# 467444_130_3_4-A.net
KiCad netlist of a schematic drawn in Altium Designer
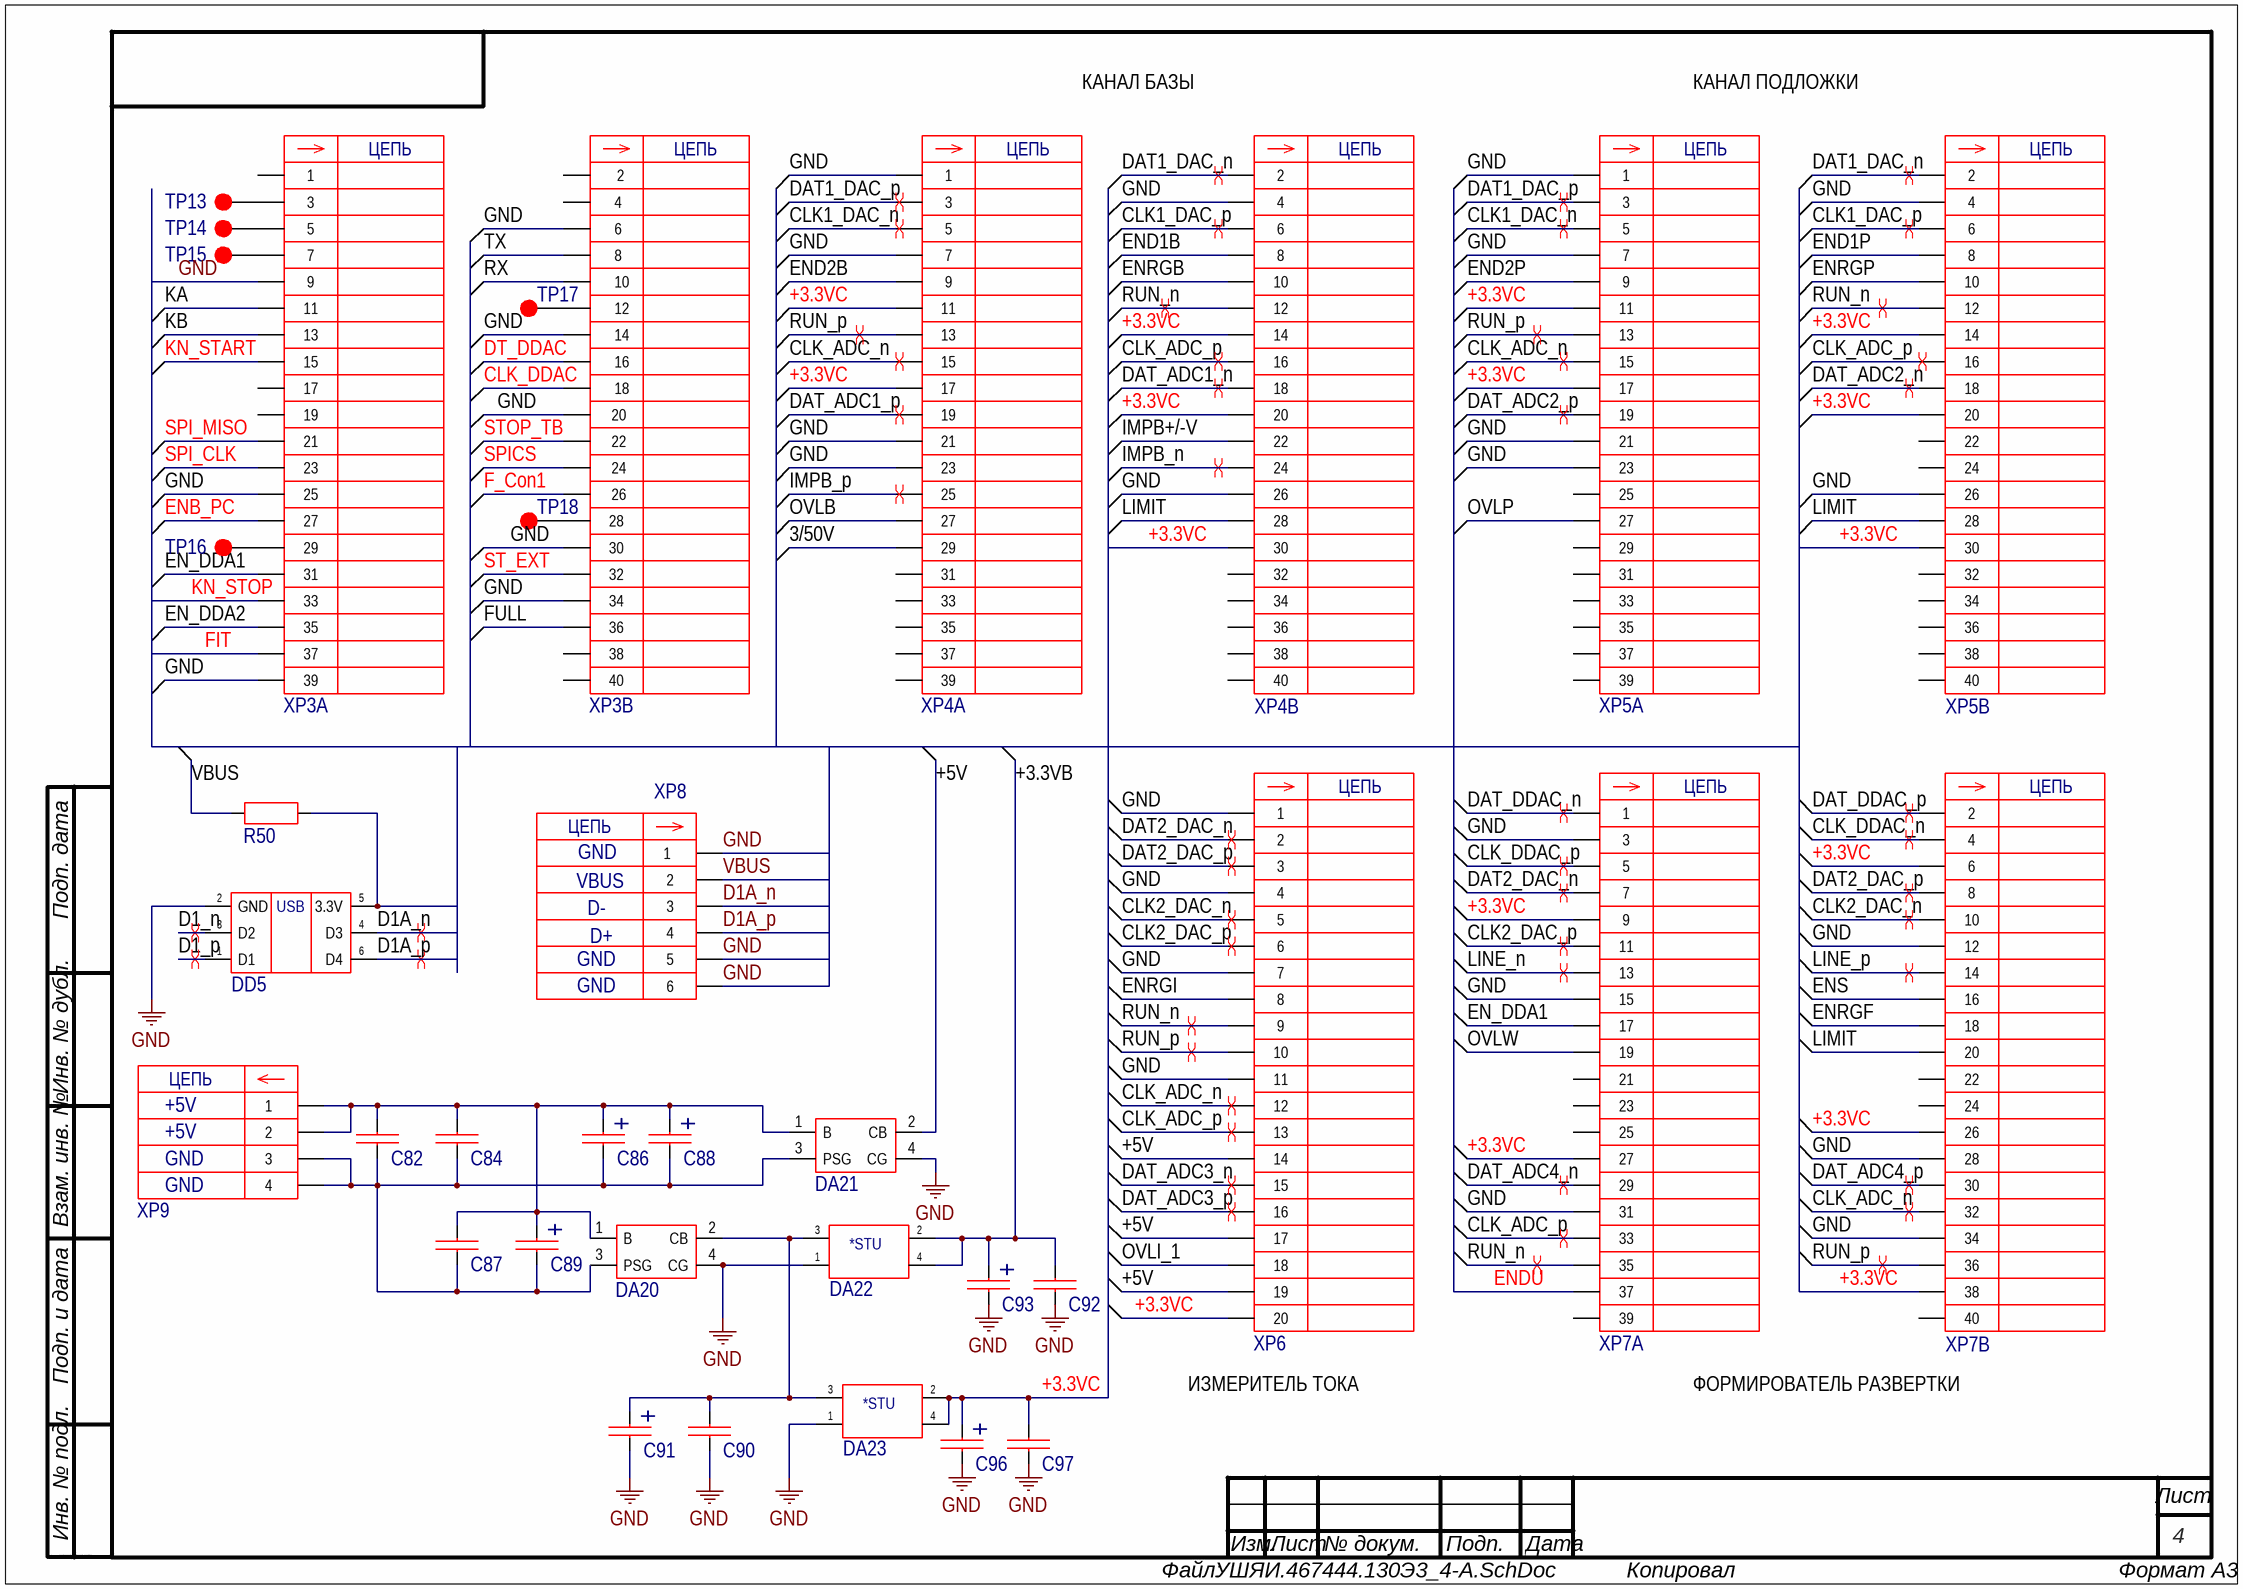
[diagram p0: УШЯИ.467444.130Э3_4-A.SchDoc]

(export (version "E")
  (design (tool "Eeschema 10.0.6"))
  (components
    (comp (ref "C82")
      (value "0,1 µF")
      (footprint "C_0805 [2012 Metric]")
      (description "Неполярный конденсатор")
      (fields (field (name "MANUFACTURER") "Murata") (field (name "VOLTAGE") "50V"))
      (libsource (lib "lib") (part "C_const"))
    )
    (comp (ref "C84")
      (value "0,1 µF")
      (footprint "C_0805 [2012 Metric]")
      (description "Неполярный конденсатор")
      (fields (field (name "MANUFACTURER") "Murata") (field (name "VOLTAGE") "50V"))
      (libsource (lib "lib") (part "C_const"))
    )
    (comp (ref "C86")
      (value "1000 µF")
      (footprint "С_EXR_10x21")
      (description "Полярный конденсатор")
      (fields (field (name "MANUFACTURER") "Hitano") (field (name "VOLTAGE") "16V"))
      (libsource (lib "lib") (part "C_electrolytic"))
    )
    (comp (ref "C87")
      (value "0,1 µF")
      (footprint "C_0805 [2012 Metric]")
      (description "Неполярный конденсатор")
      (fields (field (name "MANUFACTURER") "Murata") (field (name "VOLTAGE") "50V"))
      (libsource (lib "lib") (part "C_const"))
    )
    (comp (ref "C88")
      (value "10 µF")
      (footprint "C+_1210 [3528-21 Metric]")
      (description "Полярный конденсатор")
      (fields (field (name "MANUFACTURER") "KYOCERA AVX") (field (name "VOLTAGE") "20V\r\n10V"))
      (libsource (lib "lib") (part "C_electrolytic"))
    )
    (comp (ref "C89")
      (value "10 µF")
      (footprint "C+_1210 [3528-21 Metric]")
      (description "Полярный конденсатор")
      (fields (field (name "MANUFACTURER") "KYOCERA AVX") (field (name "VOLTAGE") "20V\r\n10V"))
      (libsource (lib "lib") (part "C_electrolytic"))
    )
    (comp (ref "C90")
      (value "0,1 µF")
      (footprint "C_0805 [2012 Metric]")
      (description "Неполярный конденсатор")
      (fields (field (name "MANUFACTURER") "Murata") (field (name "VOLTAGE") "50V"))
      (libsource (lib "lib") (part "C_const"))
    )
    (comp (ref "C91")
      (value "10 µF")
      (footprint "C+_1210 [3528-21 Metric]")
      (description "Полярный конденсатор")
      (fields (field (name "MANUFACTURER") "KYOCERA AVX") (field (name "VOLTAGE") "20V\r\n10V"))
      (libsource (lib "lib") (part "C_electrolytic"))
    )
    (comp (ref "C92")
      (value "0,1 µF")
      (footprint "C_0805 [2012 Metric]")
      (description "Неполярный конденсатор")
      (fields (field (name "MANUFACTURER") "Murata") (field (name "VOLTAGE") "50V"))
      (libsource (lib "lib") (part "C_const"))
    )
    (comp (ref "C93")
      (value "10 µF")
      (footprint "C+_1210 [3528-21 Metric]")
      (description "Полярный конденсатор")
      (fields (field (name "MANUFACTURER") "KYOCERA AVX") (field (name "VOLTAGE") "20V\r\n10V"))
      (libsource (lib "lib") (part "C_electrolytic"))
    )
    (comp (ref "C96")
      (value "10 µF")
      (footprint "C+_1210 [3528-21 Metric]")
      (description "Полярный конденсатор")
      (fields (field (name "MANUFACTURER") "KYOCERA AVX") (field (name "VOLTAGE") "20V\r\n10V"))
      (libsource (lib "lib") (part "C_electrolytic"))
    )
    (comp (ref "C97")
      (value "0,1 µF")
      (footprint "C_0805 [2012 Metric]")
      (description "Неполярный конденсатор")
      (fields (field (name "MANUFACTURER") "Murata") (field (name "VOLTAGE") "50V"))
      (libsource (lib "lib") (part "C_const"))
    )
    (comp (ref "DA20")
      (value "BNX028-01")
      (footprint "F_BNX028-01")
      (description "16В, 35дБ")
      (fields (field (name "MANUFACTURER") "Murata Electronics"))
      (libsource (lib "lib") (part "F_BNX022-01"))
    )
    (comp (ref "DA21")
      (value "BNX028-01")
      (footprint "F_BNX028-01")
      (description "16В, 35дБ")
      (fields (field (name "MANUFACTURER") "Murata Electronics"))
      (libsource (lib "lib") (part "F_BNX022-01"))
    )
    (comp (ref "DA22")
      (value "LD1117AS33TR")
      (footprint "SOT-223")
      (description "IC, Fixed LDO Voltage Regulator, 5.3V to 10V, 1.15V Dropout, 3.3Vout, 1Aout")
      (fields (field (name "MANUFACTURER") "STMicroelectronics"))
      (libsource (lib "lib") (part "VolReg_LD1117AS33TR"))
    )
    (comp (ref "DA23")
      (value "LD1117AS33TR")
      (footprint "SOT-223")
      (description "IC, Fixed LDO Voltage Regulator, 5.3V to 10V, 1.15V Dropout, 3.3Vout, 1Aout")
      (fields (field (name "MANUFACTURER") "STMicroelectronics"))
      (libsource (lib "lib") (part "VolReg_LD1117AS33TR"))
    )
    (comp (ref "DD5")
      (value "USBUF01W6")
      (footprint "SOT-323-6")
      (description "EMI Filter, 2-Channel, USB Upstream Terminator, ESD Protection")
      (fields (field (name "MANUFACTURER") "STMicroelectronics"))
      (libsource (lib "lib") (part "USBUF01W6"))
    )
    (comp (ref "R50")
      (value "30R")
      (footprint "R_0805 [2012 Metric]")
      (fields (field (name "TOLERANCE") "±5%"))
      (libsource (lib "lib") (part "R_Const"))
    )
    (comp (ref "TP13") (value "~") (footprint "DSP_1.3") (libsource (lib "lib") (part "TP")))
    (comp (ref "TP14") (value "~") (footprint "DSP_1.3") (libsource (lib "lib") (part "TP")))
    (comp (ref "TP15") (value "~") (footprint "DSP_1.3") (libsource (lib "lib") (part "TP")))
    (comp (ref "TP16") (value "~") (footprint "DSP_1.3") (libsource (lib "lib") (part "TP")))
    (comp (ref "TP17") (value "~") (footprint "DSP_1.3") (libsource (lib "lib") (part "TP")))
    (comp (ref "TP18") (value "~") (footprint "DSP_1.3") (libsource (lib "lib") (part "TP")))
    (comp (ref "XP3")
      (value "BH-40")
      (footprint "BH-40")
      (description "Male, 40 pins, 2 rows, Vertical")
      (fields (field (name "MANUFACTURER") "Connfly electronic"))
      (libsource (lib "lib") (part "M_40"))
    )
    (comp (ref "XP4")
      (value "BH2-40")
      (footprint "BH2-40")
      (description "Male, 40 pins, 2 rows, Vertical, DS1014-40, 2 mm")
      (fields (field (name "MANUFACTURER") "Connfly electronic"))
      (libsource (lib "lib") (part "M_40"))
    )
    (comp (ref "XP5")
      (value "BH2-40")
      (footprint "BH2-40")
      (description "Male, 40 pins, 2 rows, Vertical, DS1014-40, 2 mm")
      (fields (field (name "MANUFACTURER") "Connfly electronic"))
      (libsource (lib "lib") (part "M_40"))
    )
    (comp (ref "XP6")
      (value "BH2-20R")
      (footprint "BH2-20R")
      (description "Male, 20 pins, 2 rows, Right Angle, DS1014-20RF1B-B, 2 mm")
      (fields (field (name "MANUFACTURER") "Connfly electronic"))
      (libsource (lib "lib") (part "M_20"))
    )
    (comp (ref "XP7")
      (value "BH2-40")
      (footprint "BH2-40")
      (description "Male, 40 pins, 2 rows, Vertical, DS1014-40, 2 mm")
      (fields (field (name "MANUFACTURER") "Connfly electronic"))
      (libsource (lib "lib") (part "M_40"))
    )
    (comp (ref "XP8")
      (value "AMPMODU II 280372-2")
      (footprint "AMP II-280372-2")
      (description "Male, 6 pin, 1 row, Vertical, Board-to-Board, 2.54 mm")
      (fields (field (name "MANUFACTURER") "TE Connectivity"))
      (libsource (lib "Lib_MN") (part "M_6"))
    )
    (comp (ref "XP9")
      (value "AMPMODU II 280371-2")
      (footprint "AMP II-280371-2")
      (description "Male, 4 pin, 1 row, Vertical, Board-to-Board, 2.54 mm")
      (fields (field (name "MANUFACTURER") "TE Connectivity"))
      (libsource (lib "lib") (part "M_4"))
    )
  )
  (nets
    (net (code "1") (name "/+3.3VB") (class "Default")
      (node (ref "C92") (pin "2") (pinfunction "2_2") (pintype "passive"))
      (node (ref "C93") (pin "+") (pinfunction "+_+") (pintype "passive"))
      (node (ref "DA22") (pin "2") (pinfunction "VOUT_2") (pintype "passive"))
      (node (ref "DA22") (pin "4") (pinfunction "VOUT_4") (pintype "passive"))
    )
    (net (code "2") (name "/+3.3VC") (class "Default")
      (node (ref "C96") (pin "+") (pinfunction "+_+") (pintype "passive"))
      (node (ref "C97") (pin "2") (pinfunction "2_2") (pintype "passive"))
      (node (ref "DA23") (pin "2") (pinfunction "VOUT_2") (pintype "passive"))
      (node (ref "DA23") (pin "4") (pinfunction "VOUT_4") (pintype "passive"))
      (node (ref "XP4") (pin "11") (pinfunction "11_11") (pintype "passive"))
      (node (ref "XP4") (pin "14") (pinfunction "14_14") (pintype "passive"))
      (node (ref "XP4") (pin "17") (pinfunction "17_17") (pintype "passive"))
      (node (ref "XP4") (pin "20") (pinfunction "20_20") (pintype "passive"))
      (node (ref "XP4") (pin "30") (pinfunction "30_30") (pintype "passive"))
      (node (ref "XP5") (pin "11") (pinfunction "11_11") (pintype "passive"))
      (node (ref "XP5") (pin "14") (pinfunction "14_14") (pintype "passive"))
      (node (ref "XP5") (pin "17") (pinfunction "17_17") (pintype "passive"))
      (node (ref "XP5") (pin "20") (pinfunction "20_20") (pintype "passive"))
      (node (ref "XP5") (pin "30") (pinfunction "30_30") (pintype "passive"))
      (node (ref "XP6") (pin "20") (pinfunction "20_20") (pintype "passive"))
      (node (ref "XP7") (pin "26") (pinfunction "26_26") (pintype "passive"))
      (node (ref "XP7") (pin "27") (pinfunction "27_27") (pintype "passive"))
      (node (ref "XP7") (pin "38") (pinfunction "38_38") (pintype "passive"))
      (node (ref "XP7") (pin "6") (pinfunction "6_6") (pintype "passive"))
      (node (ref "XP7") (pin "9") (pinfunction "9_9") (pintype "passive"))
    )
    (net (code "3") (name "/+5V") (class "Default")
      (node (ref "DA21") (pin "2") (pinfunction "CB_2") (pintype "passive"))
      (node (ref "XP6") (pin "14") (pinfunction "14_14") (pintype "passive"))
      (node (ref "XP6") (pin "17") (pinfunction "17_17") (pintype "passive"))
      (node (ref "XP6") (pin "19") (pinfunction "19_19") (pintype "passive"))
    )
    (net (code "4") (name "/3{slash}50V") (class "Default")
      (node (ref "XP4") (pin "29") (pinfunction "29_29") (pintype "passive"))
    )
    (net (code "5") (name "/CLK1_DAC_n") (class "Default")
      (node (ref "XP4") (pin "5") (pinfunction "5_5") (pintype "passive"))
      (node (ref "XP5") (pin "5") (pinfunction "5_5") (pintype "passive"))
    )
    (net (code "6") (name "/CLK1_DAC_p") (class "Default")
      (node (ref "XP4") (pin "6") (pinfunction "6_6") (pintype "passive"))
      (node (ref "XP5") (pin "6") (pinfunction "6_6") (pintype "passive"))
    )
    (net (code "7") (name "/CLK2_DAC_n") (class "Default")
      (node (ref "XP6") (pin "5") (pinfunction "5_5") (pintype "passive"))
      (node (ref "XP7") (pin "10") (pinfunction "10_10") (pintype "passive"))
    )
    (net (code "8") (name "/CLK2_DAC_p") (class "Default")
      (node (ref "XP6") (pin "6") (pinfunction "6_6") (pintype "passive"))
      (node (ref "XP7") (pin "11") (pinfunction "11_11") (pintype "passive"))
    )
    (net (code "9") (name "/CLK_ADC_n") (class "Default")
      (node (ref "XP4") (pin "15") (pinfunction "15_15") (pintype "passive"))
      (node (ref "XP5") (pin "15") (pinfunction "15_15") (pintype "passive"))
      (node (ref "XP6") (pin "12") (pinfunction "12_12") (pintype "passive"))
      (node (ref "XP7") (pin "32") (pinfunction "32_32") (pintype "passive"))
    )
    (net (code "10") (name "/CLK_ADC_p") (class "Default")
      (node (ref "XP4") (pin "16") (pinfunction "16_16") (pintype "passive"))
      (node (ref "XP5") (pin "16") (pinfunction "16_16") (pintype "passive"))
      (node (ref "XP6") (pin "13") (pinfunction "13_13") (pintype "passive"))
      (node (ref "XP7") (pin "33") (pinfunction "33_33") (pintype "passive"))
    )
    (net (code "11") (name "/CLK_DDAC") (class "Default")
      (node (ref "XP3") (pin "18") (pinfunction "18_18") (pintype "passive"))
    )
    (net (code "12") (name "/CLK_DDAC_n") (class "Default")
      (node (ref "XP7") (pin "4") (pinfunction "4_4") (pintype "passive"))
    )
    (net (code "13") (name "/CLK_DDAC_p") (class "Default")
      (node (ref "XP7") (pin "5") (pinfunction "5_5") (pintype "passive"))
    )
    (net (code "14") (name "/D1A_n") (class "Default")
      (node (ref "DD5") (pin "4") (pinfunction "D3_4") (pintype "passive"))
      (node (ref "XP8") (pin "3") (pinfunction "3_3") (pintype "passive"))
    )
    (net (code "15") (name "/D1A_p") (class "Default")
      (node (ref "DD5") (pin "6") (pinfunction "D4_6") (pintype "passive"))
      (node (ref "XP8") (pin "4") (pinfunction "4_4") (pintype "passive"))
    )
    (net (code "16") (name "/D1_n") (class "Default")
      (node (ref "DD5") (pin "3") (pinfunction "D2_3") (pintype "passive"))
    )
    (net (code "17") (name "/D1_p") (class "Default")
      (node (ref "DD5") (pin "1") (pinfunction "D1_1") (pintype "passive"))
    )
    (net (code "18") (name "/DAT1_DAC_n") (class "Default")
      (node (ref "XP4") (pin "2") (pinfunction "2_2") (pintype "passive"))
      (node (ref "XP5") (pin "2") (pinfunction "2_2") (pintype "passive"))
    )
    (net (code "19") (name "/DAT1_DAC_p") (class "Default")
      (node (ref "XP4") (pin "3") (pinfunction "3_3") (pintype "passive"))
      (node (ref "XP5") (pin "3") (pinfunction "3_3") (pintype "passive"))
    )
    (net (code "20") (name "/DAT2_DAC_n") (class "Default")
      (node (ref "XP6") (pin "2") (pinfunction "2_2") (pintype "passive"))
      (node (ref "XP7") (pin "7") (pinfunction "7_7") (pintype "passive"))
    )
    (net (code "21") (name "/DAT2_DAC_p") (class "Default")
      (node (ref "XP6") (pin "3") (pinfunction "3_3") (pintype "passive"))
      (node (ref "XP7") (pin "8") (pinfunction "8_8") (pintype "passive"))
    )
    (net (code "22") (name "/DAT_ADC1_n") (class "Default")
      (node (ref "XP4") (pin "18") (pinfunction "18_18") (pintype "passive"))
    )
    (net (code "23") (name "/DAT_ADC1_p") (class "Default")
      (node (ref "XP4") (pin "19") (pinfunction "19_19") (pintype "passive"))
    )
    (net (code "24") (name "/DAT_ADC2_n") (class "Default")
      (node (ref "XP5") (pin "18") (pinfunction "18_18") (pintype "passive"))
    )
    (net (code "25") (name "/DAT_ADC2_p") (class "Default")
      (node (ref "XP5") (pin "19") (pinfunction "19_19") (pintype "passive"))
    )
    (net (code "26") (name "/DAT_ADC3_n") (class "Default")
      (node (ref "XP6") (pin "15") (pinfunction "15_15") (pintype "passive"))
    )
    (net (code "27") (name "/DAT_ADC3_p") (class "Default")
      (node (ref "XP6") (pin "16") (pinfunction "16_16") (pintype "passive"))
    )
    (net (code "28") (name "/DAT_ADC4_n") (class "Default")
      (node (ref "XP7") (pin "29") (pinfunction "29_29") (pintype "passive"))
    )
    (net (code "29") (name "/DAT_ADC4_p") (class "Default")
      (node (ref "XP7") (pin "30") (pinfunction "30_30") (pintype "passive"))
    )
    (net (code "30") (name "/DAT_DDAC_n") (class "Default")
      (node (ref "XP7") (pin "1") (pinfunction "1_1") (pintype "passive"))
    )
    (net (code "31") (name "/DAT_DDAC_p") (class "Default")
      (node (ref "XP7") (pin "2") (pinfunction "2_2") (pintype "passive"))
    )
    (net (code "32") (name "/DT_DDAC") (class "Default")
      (node (ref "XP3") (pin "16") (pinfunction "16_16") (pintype "passive"))
    )
    (net (code "33") (name "/ENB_PC") (class "Default")
      (node (ref "XP3") (pin "27") (pinfunction "27_27") (pintype "passive"))
    )
    (net (code "34") (name "/END1B") (class "Default")
      (node (ref "XP4") (pin "8") (pinfunction "8_8") (pintype "passive"))
    )
    (net (code "35") (name "/END1P") (class "Default")
      (node (ref "XP5") (pin "8") (pinfunction "8_8") (pintype "passive"))
    )
    (net (code "36") (name "/END2B") (class "Default")
      (node (ref "XP4") (pin "9") (pinfunction "9_9") (pintype "passive"))
    )
    (net (code "37") (name "/END2P") (class "Default")
      (node (ref "XP5") (pin "9") (pinfunction "9_9") (pintype "passive"))
    )
    (net (code "38") (name "/ENDU") (class "Default")
      (node (ref "XP7") (pin "37") (pinfunction "37_37") (pintype "passive"))
    )
    (net (code "39") (name "/ENRGB") (class "Default")
      (node (ref "XP4") (pin "10") (pinfunction "10_10") (pintype "passive"))
    )
    (net (code "40") (name "/ENRGF") (class "Default")
      (node (ref "XP7") (pin "18") (pinfunction "18_18") (pintype "passive"))
    )
    (net (code "41") (name "/ENRGI") (class "Default")
      (node (ref "XP6") (pin "8") (pinfunction "8_8") (pintype "passive"))
    )
    (net (code "42") (name "/ENRGP") (class "Default")
      (node (ref "XP5") (pin "10") (pinfunction "10_10") (pintype "passive"))
    )
    (net (code "43") (name "/ENS") (class "Default")
      (node (ref "XP7") (pin "16") (pinfunction "16_16") (pintype "passive"))
    )
    (net (code "44") (name "/EN_DDA1") (class "Default")
      (node (ref "XP3") (pin "31") (pinfunction "31_31") (pintype "passive"))
      (node (ref "XP7") (pin "17") (pinfunction "17_17") (pintype "passive"))
    )
    (net (code "45") (name "/EN_DDA2") (class "Default")
      (node (ref "XP3") (pin "35") (pinfunction "35_35") (pintype "passive"))
    )
    (net (code "46") (name "/FIT") (class "Default")
      (node (ref "XP3") (pin "37") (pinfunction "37_37") (pintype "passive"))
    )
    (net (code "47") (name "/FULL") (class "Default")
      (node (ref "XP3") (pin "36") (pinfunction "36_36") (pintype "passive"))
    )
    (net (code "48") (name "/F_Con1") (class "Default")
      (node (ref "XP3") (pin "26") (pinfunction "26_26") (pintype "passive"))
    )
    (net (code "49") (name "/IMPB+{slash}-V") (class "Default")
      (node (ref "XP4") (pin "22") (pinfunction "22_22") (pintype "passive"))
    )
    (net (code "50") (name "/IMPB_n") (class "Default")
      (node (ref "XP4") (pin "24") (pinfunction "24_24") (pintype "passive"))
    )
    (net (code "51") (name "/IMPB_p") (class "Default")
      (node (ref "XP4") (pin "25") (pinfunction "25_25") (pintype "passive"))
    )
    (net (code "52") (name "/KA") (class "Default")
      (node (ref "XP3") (pin "11") (pinfunction "11_11") (pintype "passive"))
    )
    (net (code "53") (name "/KB") (class "Default")
      (node (ref "XP3") (pin "13") (pinfunction "13_13") (pintype "passive"))
    )
    (net (code "54") (name "/KN_START") (class "Default")
      (node (ref "XP3") (pin "15") (pinfunction "15_15") (pintype "passive"))
    )
    (net (code "55") (name "/KN_STOP") (class "Default")
      (node (ref "XP3") (pin "33") (pinfunction "33_33") (pintype "passive"))
    )
    (net (code "56") (name "/LIMIT") (class "Default")
      (node (ref "XP4") (pin "28") (pinfunction "28_28") (pintype "passive"))
      (node (ref "XP5") (pin "28") (pinfunction "28_28") (pintype "passive"))
      (node (ref "XP7") (pin "20") (pinfunction "20_20") (pintype "passive"))
    )
    (net (code "57") (name "/LINE_n") (class "Default")
      (node (ref "XP7") (pin "13") (pinfunction "13_13") (pintype "passive"))
    )
    (net (code "58") (name "/LINE_p") (class "Default")
      (node (ref "XP7") (pin "14") (pinfunction "14_14") (pintype "passive"))
    )
    (net (code "59") (name "/OVLB") (class "Default")
      (node (ref "XP4") (pin "27") (pinfunction "27_27") (pintype "passive"))
    )
    (net (code "60") (name "/OVLI_1") (class "Default")
      (node (ref "XP6") (pin "18") (pinfunction "18_18") (pintype "passive"))
    )
    (net (code "61") (name "/OVLP") (class "Default")
      (node (ref "XP5") (pin "27") (pinfunction "27_27") (pintype "passive"))
    )
    (net (code "62") (name "/OVLW") (class "Default")
      (node (ref "XP7") (pin "19") (pinfunction "19_19") (pintype "passive"))
    )
    (net (code "63") (name "/RUN_n") (class "Default")
      (node (ref "XP4") (pin "12") (pinfunction "12_12") (pintype "passive"))
      (node (ref "XP5") (pin "12") (pinfunction "12_12") (pintype "passive"))
      (node (ref "XP6") (pin "9") (pinfunction "9_9") (pintype "passive"))
      (node (ref "XP7") (pin "35") (pinfunction "35_35") (pintype "passive"))
    )
    (net (code "64") (name "/RUN_p") (class "Default")
      (node (ref "XP4") (pin "13") (pinfunction "13_13") (pintype "passive"))
      (node (ref "XP5") (pin "13") (pinfunction "13_13") (pintype "passive"))
      (node (ref "XP6") (pin "10") (pinfunction "10_10") (pintype "passive"))
      (node (ref "XP7") (pin "36") (pinfunction "36_36") (pintype "passive"))
    )
    (net (code "65") (name "/RX") (class "Default")
      (node (ref "XP3") (pin "10") (pinfunction "10_10") (pintype "passive"))
    )
    (net (code "66") (name "/SPICS") (class "Default")
      (node (ref "XP3") (pin "24") (pinfunction "24_24") (pintype "passive"))
    )
    (net (code "67") (name "/SPI_CLK") (class "Default")
      (node (ref "XP3") (pin "23") (pinfunction "23_23") (pintype "passive"))
    )
    (net (code "68") (name "/SPI_MISO") (class "Default")
      (node (ref "XP3") (pin "21") (pinfunction "21_21") (pintype "passive"))
    )
    (net (code "69") (name "/STOP_TB") (class "Default")
      (node (ref "XP3") (pin "22") (pinfunction "22_22") (pintype "passive"))
    )
    (net (code "70") (name "/ST_EXT") (class "Default")
      (node (ref "XP3") (pin "32") (pinfunction "32_32") (pintype "passive"))
    )
    (net (code "71") (name "/TX") (class "Default")
      (node (ref "XP3") (pin "8") (pinfunction "8_8") (pintype "passive"))
    )
    (net (code "72") (name "/VBUS") (class "Default")
      (node (ref "R50") (pin "1") (pinfunction "1_1") (pintype "passive"))
      (node (ref "XP8") (pin "2") (pinfunction "2_2") (pintype "passive"))
    )
    (net (code "73") (name "GND") (class "Default")
      (node (ref "C90") (pin "2") (pinfunction "2_2") (pintype "passive"))
      (node (ref "C91") (pin "-") (pinfunction "-_-") (pintype "passive"))
      (node (ref "C92") (pin "1") (pinfunction "1_1") (pintype "passive"))
      (node (ref "C93") (pin "-") (pinfunction "-_-") (pintype "passive"))
      (node (ref "C96") (pin "-") (pinfunction "-_-") (pintype "passive"))
      (node (ref "C97") (pin "1") (pinfunction "1_1") (pintype "passive"))
      (node (ref "DA20") (pin "4") (pinfunction "CG_4") (pintype "passive"))
      (node (ref "DA21") (pin "4") (pinfunction "CG_4") (pintype "passive"))
      (node (ref "DA22") (pin "1") (pinfunction "ADJ/GND_1") (pintype "passive"))
      (node (ref "DA23") (pin "1") (pinfunction "ADJ/GND_1") (pintype "passive"))
      (node (ref "DD5") (pin "2") (pinfunction "GND_2") (pintype "passive"))
      (node (ref "XP3") (pin "14") (pinfunction "14_14") (pintype "passive"))
      (node (ref "XP3") (pin "20") (pinfunction "20_20") (pintype "passive"))
      (node (ref "XP3") (pin "25") (pinfunction "25_25") (pintype "passive"))
      (node (ref "XP3") (pin "30") (pinfunction "30_30") (pintype "passive"))
      (node (ref "XP3") (pin "34") (pinfunction "34_34") (pintype "passive"))
      (node (ref "XP3") (pin "39") (pinfunction "39_39") (pintype "passive"))
      (node (ref "XP3") (pin "6") (pinfunction "6_6") (pintype "passive"))
      (node (ref "XP3") (pin "9") (pinfunction "9_9") (pintype "passive"))
      (node (ref "XP4") (pin "1") (pinfunction "1_1") (pintype "passive"))
      (node (ref "XP4") (pin "21") (pinfunction "21_21") (pintype "passive"))
      (node (ref "XP4") (pin "23") (pinfunction "23_23") (pintype "passive"))
      (node (ref "XP4") (pin "26") (pinfunction "26_26") (pintype "passive"))
      (node (ref "XP4") (pin "4") (pinfunction "4_4") (pintype "passive"))
      (node (ref "XP4") (pin "7") (pinfunction "7_7") (pintype "passive"))
      (node (ref "XP5") (pin "1") (pinfunction "1_1") (pintype "passive"))
      (node (ref "XP5") (pin "21") (pinfunction "21_21") (pintype "passive"))
      (node (ref "XP5") (pin "23") (pinfunction "23_23") (pintype "passive"))
      (node (ref "XP5") (pin "26") (pinfunction "26_26") (pintype "passive"))
      (node (ref "XP5") (pin "4") (pinfunction "4_4") (pintype "passive"))
      (node (ref "XP5") (pin "7") (pinfunction "7_7") (pintype "passive"))
      (node (ref "XP6") (pin "1") (pinfunction "1_1") (pintype "passive"))
      (node (ref "XP6") (pin "11") (pinfunction "11_11") (pintype "passive"))
      (node (ref "XP6") (pin "4") (pinfunction "4_4") (pintype "passive"))
      (node (ref "XP6") (pin "7") (pinfunction "7_7") (pintype "passive"))
      (node (ref "XP7") (pin "12") (pinfunction "12_12") (pintype "passive"))
      (node (ref "XP7") (pin "15") (pinfunction "15_15") (pintype "passive"))
      (node (ref "XP7") (pin "28") (pinfunction "28_28") (pintype "passive"))
      (node (ref "XP7") (pin "3") (pinfunction "3_3") (pintype "passive"))
      (node (ref "XP7") (pin "31") (pinfunction "31_31") (pintype "passive"))
      (node (ref "XP7") (pin "34") (pinfunction "34_34") (pintype "passive"))
      (node (ref "XP8") (pin "1") (pinfunction "1_1") (pintype "passive"))
      (node (ref "XP8") (pin "5") (pinfunction "5_5") (pintype "passive"))
      (node (ref "XP8") (pin "6") (pinfunction "6_6") (pintype "passive"))
    )
    (net (code "74") (name "Net-(DA20-B)") (class "Default")
      (node (ref "C82") (pin "1") (pinfunction "1_1") (pintype "passive"))
      (node (ref "C84") (pin "1") (pinfunction "1_1") (pintype "passive"))
      (node (ref "C86") (pin "+") (pinfunction "+_+") (pintype "passive"))
      (node (ref "C87") (pin "2") (pinfunction "2_2") (pintype "passive"))
      (node (ref "C88") (pin "+") (pinfunction "+_+") (pintype "passive"))
      (node (ref "C89") (pin "+") (pinfunction "+_+") (pintype "passive"))
      (node (ref "DA20") (pin "1") (pinfunction "B_1") (pintype "passive"))
      (node (ref "DA21") (pin "1") (pinfunction "B_1") (pintype "passive"))
      (node (ref "XP9") (pin "1") (pinfunction "1_1") (pintype "passive"))
      (node (ref "XP9") (pin "2") (pinfunction "2_2") (pintype "passive"))
    )
    (net (code "75") (name "Net-(DA20-CB)") (class "Default")
      (node (ref "C90") (pin "1") (pinfunction "1_1") (pintype "passive"))
      (node (ref "C91") (pin "+") (pinfunction "+_+") (pintype "passive"))
      (node (ref "DA20") (pin "2") (pinfunction "CB_2") (pintype "passive"))
      (node (ref "DA22") (pin "3") (pinfunction "VIN_3") (pintype "passive"))
      (node (ref "DA23") (pin "3") (pinfunction "VIN_3") (pintype "passive"))
    )
    (net (code "76") (name "Net-(DA20-PSG)") (class "Default")
      (node (ref "C82") (pin "2") (pinfunction "2_2") (pintype "passive"))
      (node (ref "C84") (pin "2") (pinfunction "2_2") (pintype "passive"))
      (node (ref "C86") (pin "-") (pinfunction "-_-") (pintype "passive"))
      (node (ref "C87") (pin "1") (pinfunction "1_1") (pintype "passive"))
      (node (ref "C88") (pin "-") (pinfunction "-_-") (pintype "passive"))
      (node (ref "C89") (pin "-") (pinfunction "-_-") (pintype "passive"))
      (node (ref "DA20") (pin "3") (pinfunction "PSG_3") (pintype "passive"))
      (node (ref "DA21") (pin "3") (pinfunction "PSG_3") (pintype "passive"))
      (node (ref "XP9") (pin "3") (pinfunction "3_3") (pintype "passive"))
      (node (ref "XP9") (pin "4") (pinfunction "4_4") (pintype "passive"))
    )
    (net (code "77") (name "Net-(DD5-3.3V)") (class "Default")
      (node (ref "DD5") (pin "5") (pinfunction "3.3V_5") (pintype "passive"))
      (node (ref "R50") (pin "2") (pinfunction "2_2") (pintype "passive"))
    )
    (net (code "78") (name "Net-(TP13-Pad1)") (class "Default")
      (node (ref "TP13") (pin "1") (pinfunction "1_1") (pintype "passive"))
      (node (ref "XP3") (pin "3") (pinfunction "3_3") (pintype "passive"))
    )
    (net (code "79") (name "Net-(TP14-Pad1)") (class "Default")
      (node (ref "TP14") (pin "1") (pinfunction "1_1") (pintype "passive"))
      (node (ref "XP3") (pin "5") (pinfunction "5_5") (pintype "passive"))
    )
    (net (code "80") (name "Net-(TP15-Pad1)") (class "Default")
      (node (ref "TP15") (pin "1") (pinfunction "1_1") (pintype "passive"))
      (node (ref "XP3") (pin "7") (pinfunction "7_7") (pintype "passive"))
    )
    (net (code "81") (name "Net-(TP16-Pad1)") (class "Default")
      (node (ref "TP16") (pin "1") (pinfunction "1_1") (pintype "passive"))
      (node (ref "XP3") (pin "29") (pinfunction "29_29") (pintype "passive"))
    )
    (net (code "82") (name "Net-(TP17-Pad1)") (class "Default")
      (node (ref "TP17") (pin "1") (pinfunction "1_1") (pintype "passive"))
      (node (ref "XP3") (pin "12") (pinfunction "12_12") (pintype "passive"))
    )
    (net (code "83") (name "Net-(TP18-Pad1)") (class "Default")
      (node (ref "TP18") (pin "1") (pinfunction "1_1") (pintype "passive"))
      (node (ref "XP3") (pin "28") (pinfunction "28_28") (pintype "passive"))
    )
    (net (code "84") (name "unconnected-(XP3-Pad1)") (class "Default")
      (node (ref "XP3") (pin "1") (pinfunction "1_1") (pintype "passive"))
    )
    (net (code "85") (name "unconnected-(XP3-Pad2)") (class "Default")
      (node (ref "XP3") (pin "2") (pinfunction "2_2") (pintype "passive"))
    )
    (net (code "86") (name "unconnected-(XP3-Pad4)") (class "Default")
      (node (ref "XP3") (pin "4") (pinfunction "4_4") (pintype "passive"))
    )
    (net (code "87") (name "unconnected-(XP3-Pad17)") (class "Default")
      (node (ref "XP3") (pin "17") (pinfunction "17_17") (pintype "passive"))
    )
    (net (code "88") (name "unconnected-(XP3-Pad19)") (class "Default")
      (node (ref "XP3") (pin "19") (pinfunction "19_19") (pintype "passive"))
    )
    (net (code "89") (name "unconnected-(XP3-Pad38)") (class "Default")
      (node (ref "XP3") (pin "38") (pinfunction "38_38") (pintype "passive"))
    )
    (net (code "90") (name "unconnected-(XP3-Pad40)") (class "Default")
      (node (ref "XP3") (pin "40") (pinfunction "40_40") (pintype "passive"))
    )
    (net (code "91") (name "unconnected-(XP4-Pad31)") (class "Default")
      (node (ref "XP4") (pin "31") (pinfunction "31_31") (pintype "passive"))
    )
    (net (code "92") (name "unconnected-(XP4-Pad32)") (class "Default")
      (node (ref "XP4") (pin "32") (pinfunction "32_32") (pintype "passive"))
    )
    (net (code "93") (name "unconnected-(XP4-Pad33)") (class "Default")
      (node (ref "XP4") (pin "33") (pinfunction "33_33") (pintype "passive"))
    )
    (net (code "94") (name "unconnected-(XP4-Pad34)") (class "Default")
      (node (ref "XP4") (pin "34") (pinfunction "34_34") (pintype "passive"))
    )
    (net (code "95") (name "unconnected-(XP4-Pad35)") (class "Default")
      (node (ref "XP4") (pin "35") (pinfunction "35_35") (pintype "passive"))
    )
    (net (code "96") (name "unconnected-(XP4-Pad36)") (class "Default")
      (node (ref "XP4") (pin "36") (pinfunction "36_36") (pintype "passive"))
    )
    (net (code "97") (name "unconnected-(XP4-Pad37)") (class "Default")
      (node (ref "XP4") (pin "37") (pinfunction "37_37") (pintype "passive"))
    )
    (net (code "98") (name "unconnected-(XP4-Pad38)") (class "Default")
      (node (ref "XP4") (pin "38") (pinfunction "38_38") (pintype "passive"))
    )
    (net (code "99") (name "unconnected-(XP4-Pad39)") (class "Default")
      (node (ref "XP4") (pin "39") (pinfunction "39_39") (pintype "passive"))
    )
    (net (code "100") (name "unconnected-(XP4-Pad40)") (class "Default")
      (node (ref "XP4") (pin "40") (pinfunction "40_40") (pintype "passive"))
    )
    (net (code "101") (name "unconnected-(XP5-Pad22)") (class "Default")
      (node (ref "XP5") (pin "22") (pinfunction "22_22") (pintype "passive"))
    )
    (net (code "102") (name "unconnected-(XP5-Pad24)") (class "Default")
      (node (ref "XP5") (pin "24") (pinfunction "24_24") (pintype "passive"))
    )
    (net (code "103") (name "unconnected-(XP5-Pad25)") (class "Default")
      (node (ref "XP5") (pin "25") (pinfunction "25_25") (pintype "passive"))
    )
    (net (code "104") (name "unconnected-(XP5-Pad29)") (class "Default")
      (node (ref "XP5") (pin "29") (pinfunction "29_29") (pintype "passive"))
    )
    (net (code "105") (name "unconnected-(XP5-Pad31)") (class "Default")
      (node (ref "XP5") (pin "31") (pinfunction "31_31") (pintype "passive"))
    )
    (net (code "106") (name "unconnected-(XP5-Pad32)") (class "Default")
      (node (ref "XP5") (pin "32") (pinfunction "32_32") (pintype "passive"))
    )
    (net (code "107") (name "unconnected-(XP5-Pad33)") (class "Default")
      (node (ref "XP5") (pin "33") (pinfunction "33_33") (pintype "passive"))
    )
    (net (code "108") (name "unconnected-(XP5-Pad34)") (class "Default")
      (node (ref "XP5") (pin "34") (pinfunction "34_34") (pintype "passive"))
    )
    (net (code "109") (name "unconnected-(XP5-Pad35)") (class "Default")
      (node (ref "XP5") (pin "35") (pinfunction "35_35") (pintype "passive"))
    )
    (net (code "110") (name "unconnected-(XP5-Pad36)") (class "Default")
      (node (ref "XP5") (pin "36") (pinfunction "36_36") (pintype "passive"))
    )
    (net (code "111") (name "unconnected-(XP5-Pad37)") (class "Default")
      (node (ref "XP5") (pin "37") (pinfunction "37_37") (pintype "passive"))
    )
    (net (code "112") (name "unconnected-(XP5-Pad38)") (class "Default")
      (node (ref "XP5") (pin "38") (pinfunction "38_38") (pintype "passive"))
    )
    (net (code "113") (name "unconnected-(XP5-Pad39)") (class "Default")
      (node (ref "XP5") (pin "39") (pinfunction "39_39") (pintype "passive"))
    )
    (net (code "114") (name "unconnected-(XP5-Pad40)") (class "Default")
      (node (ref "XP5") (pin "40") (pinfunction "40_40") (pintype "passive"))
    )
    (net (code "115") (name "unconnected-(XP7-Pad21)") (class "Default")
      (node (ref "XP7") (pin "21") (pinfunction "21_21") (pintype "passive"))
    )
    (net (code "116") (name "unconnected-(XP7-Pad22)") (class "Default")
      (node (ref "XP7") (pin "22") (pinfunction "22_22") (pintype "passive"))
    )
    (net (code "117") (name "unconnected-(XP7-Pad23)") (class "Default")
      (node (ref "XP7") (pin "23") (pinfunction "23_23") (pintype "passive"))
    )
    (net (code "118") (name "unconnected-(XP7-Pad24)") (class "Default")
      (node (ref "XP7") (pin "24") (pinfunction "24_24") (pintype "passive"))
    )
    (net (code "119") (name "unconnected-(XP7-Pad25)") (class "Default")
      (node (ref "XP7") (pin "25") (pinfunction "25_25") (pintype "passive"))
    )
    (net (code "120") (name "unconnected-(XP7-Pad39)") (class "Default")
      (node (ref "XP7") (pin "39") (pinfunction "39_39") (pintype "passive"))
    )
    (net (code "121") (name "unconnected-(XP7-Pad40)") (class "Default")
      (node (ref "XP7") (pin "40") (pinfunction "40_40") (pintype "passive"))
    )
  )
)
